# Portable_iron_V3_0.net
KiCad netlist of a schematic drawn in Altium Designer
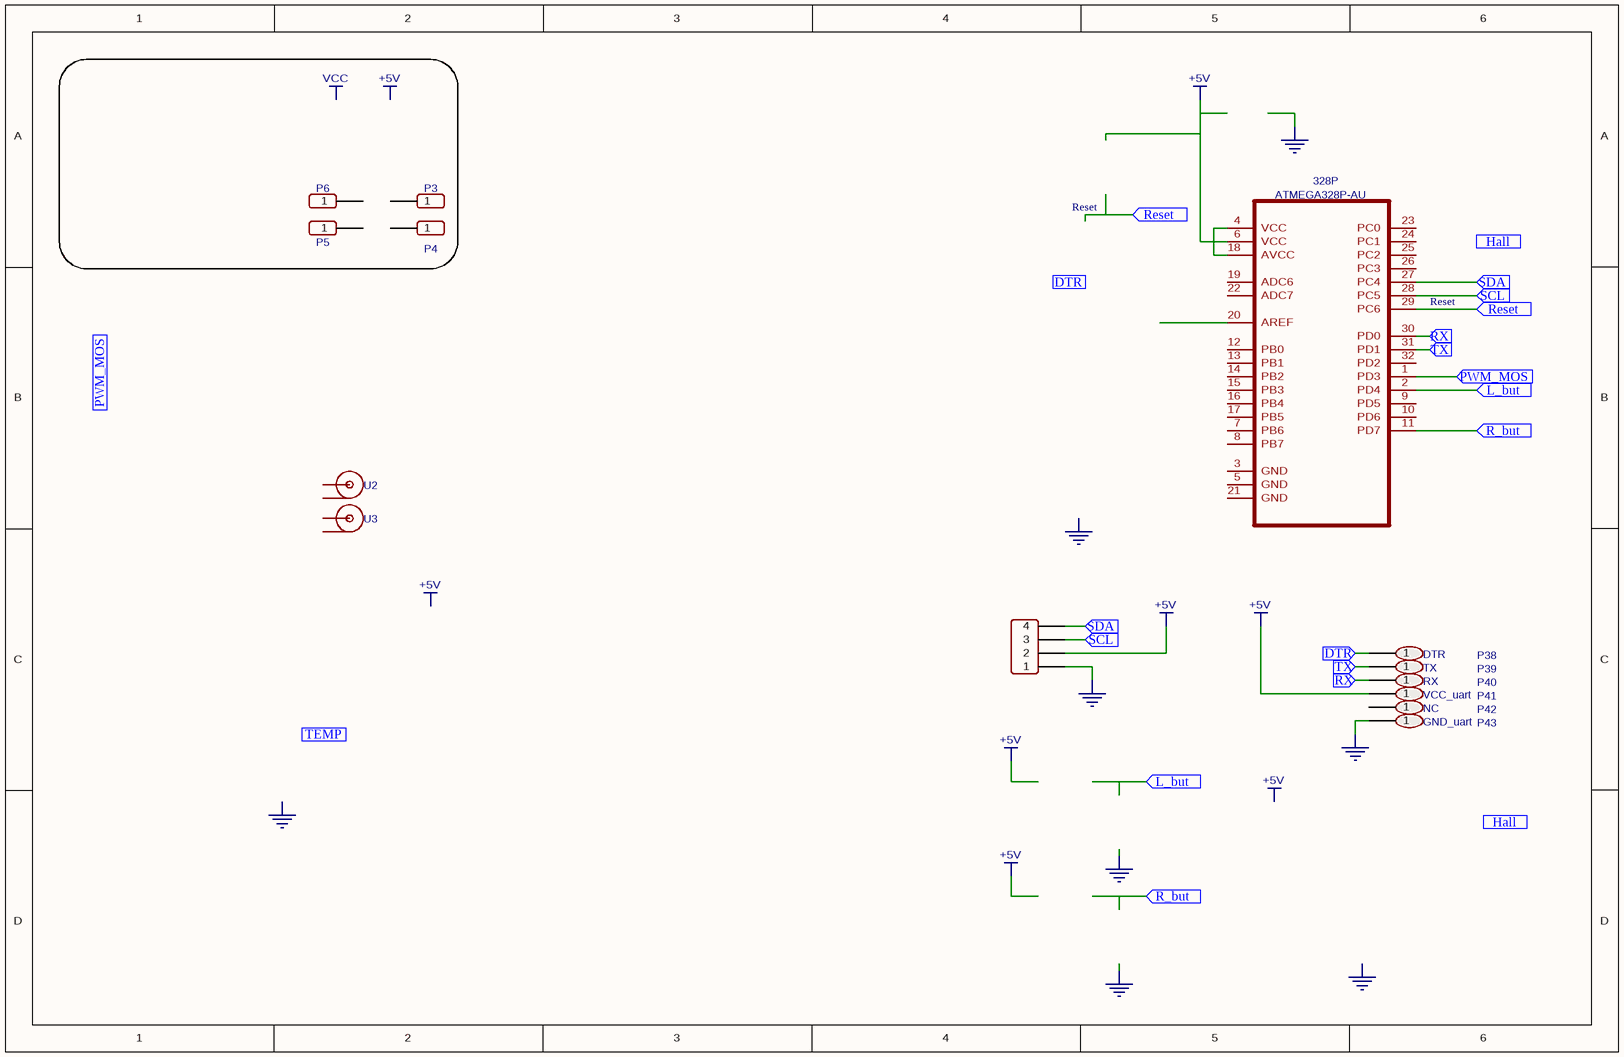
[diagram p0: Portable iron V3.0 .schdoc]

(export (version "E")
  (design (tool "Eeschema 10.0.6"))
  (components
    (comp (ref "328P")
      (value "ATMEGA328P-AU")
      (fields (field (name "BOM_MANUFACTURER PART") "?"))
      (libsource (lib "altium-import") (part "root_0_ATMEGA328P-AU_"))
    )
    (comp (ref "P1")
      (value "i2c_OLED")
      (fields
        (field (name "BOM_MANUFACTURER PART") "Headers  Pins 1*4P")
        (field (name "BOM_SUPPLIER PART") "undefined")
      )
      (libsource (lib "altium-import") (part "root_2_i2c_OLED_"))
    )
    (comp (ref "P3")
      (value "Header 1*1P")
      (fields (field (name "BOM_SUPPLIER PART") "C81276"))
      (libsource (lib "altium-import") (part "root_0_Header 1*1P_"))
    )
    (comp (ref "P4")
      (value "Header 1*1P")
      (fields (field (name "BOM_SUPPLIER PART") "C81276"))
      (libsource (lib "altium-import") (part "root_0_Header 1*1P_"))
    )
    (comp (ref "P5")
      (value "Header 1*1P")
      (fields (field (name "BOM_SUPPLIER PART") "C81276"))
      (libsource (lib "altium-import") (part "root_2_Header 1*1P_"))
    )
    (comp (ref "P6")
      (value "Header 1*1P")
      (fields (field (name "BOM_SUPPLIER PART") "C81276"))
      (libsource (lib "altium-import") (part "root_2_Header 1*1P_"))
    )
    (comp (ref "P38")
      (value "DTR")
      (fields
        (field (name "BOM_MANUFACTURER PART") "Header 1*1P")
        (field (name "BOM_SUPPLIER PART") "C81276")
      )
      (libsource (lib "altium-import") (part "root_0_DTR_"))
    )
    (comp (ref "P39")
      (value "TX")
      (fields
        (field (name "BOM_MANUFACTURER PART") "Header 1*1P")
        (field (name "BOM_SUPPLIER PART") "C81276")
      )
      (libsource (lib "altium-import") (part "root_0_TX_"))
    )
    (comp (ref "P40")
      (value "RX")
      (fields
        (field (name "BOM_MANUFACTURER PART") "Header 1*1P")
        (field (name "BOM_SUPPLIER PART") "C81276")
      )
      (libsource (lib "altium-import") (part "root_0_RX_"))
    )
    (comp (ref "P41")
      (value "VCC_uart")
      (fields
        (field (name "BOM_MANUFACTURER PART") "Header 1*1P")
        (field (name "BOM_SUPPLIER PART") "C81276")
      )
      (libsource (lib "altium-import") (part "root_0_VCC_uart_"))
    )
    (comp (ref "P42")
      (value "NC")
      (fields
        (field (name "BOM_MANUFACTURER PART") "Header 1*1P")
        (field (name "BOM_SUPPLIER PART") "C81276")
      )
      (libsource (lib "altium-import") (part "root_0_NC_"))
    )
    (comp (ref "P43")
      (value "GND_uart")
      (fields
        (field (name "BOM_MANUFACTURER PART") "Header 1*1P")
        (field (name "BOM_SUPPLIER PART") "C81276")
      )
      (libsource (lib "altium-import") (part "root_0_GND_uart_"))
    )
    (comp (ref "U2")
      (value "Fuse clip 1p TH")
      (fields
        (field (name "BOM_MANUFACTURER PART") "5x20 RHOS Fuse clip/seat")
        (field (name "BOM_SUPPLIER PART") "C3130")
        (field (name "CONTRIBUTOR") "gjt211")
      )
      (libsource (lib "altium-import") (part "root_0_Fuse clip 1p TH_"))
    )
    (comp (ref "U3")
      (value "Fuse clip 1p TH")
      (fields
        (field (name "BOM_MANUFACTURER PART") "5x20 RHOS Fuse clip/seat")
        (field (name "BOM_SUPPLIER PART") "C3130")
        (field (name "CONTRIBUTOR") "gjt211")
      )
      (libsource (lib "altium-import") (part "root_0_Fuse clip 1p TH_"))
    )
  )
  (nets
    (net (code "1") (name "+5V") (class "Default")
      (node (ref "328P") (pin "18") (pinfunction "AVCC_18") (pintype "passive"))
      (node (ref "328P") (pin "4") (pinfunction "VCC_4") (pintype "passive"))
      (node (ref "328P") (pin "6") (pinfunction "VCC_6") (pintype "passive"))
      (node (ref "P1") (pin "2") (pinfunction "2_2") (pintype "passive"))
      (node (ref "P41") (pin "1") (pinfunction "1_1") (pintype "passive"))
    )
    (net (code "2") (name "/DTR") (class "Default")
      (node (ref "P38") (pin "1") (pinfunction "1_1") (pintype "passive"))
    )
    (net (code "4") (name "/L_but") (class "Default")
      (node (ref "328P") (pin "2") (pinfunction "PD4_2") (pintype "passive"))
    )
    (net (code "5") (name "/PWM_MOS") (class "Default")
      (node (ref "328P") (pin "1") (pinfunction "PD3_1") (pintype "passive"))
    )
    (net (code "6") (name "/RX") (class "Default")
      (node (ref "328P") (pin "30") (pinfunction "PD0_30") (pintype "passive"))
      (node (ref "P40") (pin "1") (pinfunction "1_1") (pintype "passive"))
    )
    (net (code "7") (name "/R_but") (class "Default")
      (node (ref "328P") (pin "11") (pinfunction "PD7_11") (pintype "passive"))
    )
    (net (code "8") (name "/Reset") (class "Default")
      (node (ref "328P") (pin "29") (pinfunction "PC6_29") (pintype "passive"))
    )
    (net (code "9") (name "/SCL") (class "Default")
      (node (ref "328P") (pin "28") (pinfunction "PC5_28") (pintype "passive"))
      (node (ref "P1") (pin "3") (pinfunction "3_3") (pintype "passive"))
    )
    (net (code "10") (name "/SDA") (class "Default")
      (node (ref "328P") (pin "27") (pinfunction "PC4_27") (pintype "passive"))
      (node (ref "P1") (pin "4") (pinfunction "4_4") (pintype "passive"))
    )
    (net (code "12") (name "/TX") (class "Default")
      (node (ref "328P") (pin "31") (pinfunction "PD1_31") (pintype "passive"))
      (node (ref "P39") (pin "1") (pinfunction "1_1") (pintype "passive"))
    )
    (net (code "13") (name "GND") (class "Default")
      (node (ref "P1") (pin "1") (pinfunction "1_1") (pintype "passive"))
      (node (ref "P43") (pin "1") (pinfunction "1_1") (pintype "passive"))
    )
    (net (code "15") (name "unconnected-(328P-ADC6-Pad19)") (class "Default")
      (node (ref "328P") (pin "19") (pinfunction "ADC6_19") (pintype "passive"))
    )
    (net (code "16") (name "unconnected-(328P-ADC7-Pad22)") (class "Default")
      (node (ref "328P") (pin "22") (pinfunction "ADC7_22") (pintype "passive"))
    )
    (net (code "17") (name "unconnected-(328P-AREF-Pad20)") (class "Default")
      (node (ref "328P") (pin "20") (pinfunction "AREF_20") (pintype "passive"))
    )
    (net (code "18") (name "unconnected-(328P-GND-Pad3)") (class "Default")
      (node (ref "328P") (pin "3") (pinfunction "GND_3") (pintype "passive"))
    )
    (net (code "19") (name "unconnected-(328P-GND-Pad5)") (class "Default")
      (node (ref "328P") (pin "5") (pinfunction "GND_5") (pintype "passive"))
    )
    (net (code "20") (name "unconnected-(328P-GND-Pad21)") (class "Default")
      (node (ref "328P") (pin "21") (pinfunction "GND_21") (pintype "passive"))
    )
    (net (code "21") (name "unconnected-(328P-PB0-Pad12)") (class "Default")
      (node (ref "328P") (pin "12") (pinfunction "PB0_12") (pintype "passive"))
    )
    (net (code "22") (name "unconnected-(328P-PB1-Pad13)") (class "Default")
      (node (ref "328P") (pin "13") (pinfunction "PB1_13") (pintype "passive"))
    )
    (net (code "23") (name "unconnected-(328P-PB2-Pad14)") (class "Default")
      (node (ref "328P") (pin "14") (pinfunction "PB2_14") (pintype "passive"))
    )
    (net (code "24") (name "unconnected-(328P-PB3-Pad15)") (class "Default")
      (node (ref "328P") (pin "15") (pinfunction "PB3_15") (pintype "passive"))
    )
    (net (code "25") (name "unconnected-(328P-PB4-Pad16)") (class "Default")
      (node (ref "328P") (pin "16") (pinfunction "PB4_16") (pintype "passive"))
    )
    (net (code "26") (name "unconnected-(328P-PB5-Pad17)") (class "Default")
      (node (ref "328P") (pin "17") (pinfunction "PB5_17") (pintype "passive"))
    )
    (net (code "27") (name "unconnected-(328P-PB6-Pad7)") (class "Default")
      (node (ref "328P") (pin "7") (pinfunction "PB6_7") (pintype "passive"))
    )
    (net (code "28") (name "unconnected-(328P-PB7-Pad8)") (class "Default")
      (node (ref "328P") (pin "8") (pinfunction "PB7_8") (pintype "passive"))
    )
    (net (code "29") (name "unconnected-(328P-PC0-Pad23)") (class "Default")
      (node (ref "328P") (pin "23") (pinfunction "PC0_23") (pintype "passive"))
    )
    (net (code "30") (name "unconnected-(328P-PC1-Pad24)") (class "Default")
      (node (ref "328P") (pin "24") (pinfunction "PC1_24") (pintype "passive"))
    )
    (net (code "31") (name "unconnected-(328P-PC2-Pad25)") (class "Default")
      (node (ref "328P") (pin "25") (pinfunction "PC2_25") (pintype "passive"))
    )
    (net (code "32") (name "unconnected-(328P-PC3-Pad26)") (class "Default")
      (node (ref "328P") (pin "26") (pinfunction "PC3_26") (pintype "passive"))
    )
    (net (code "33") (name "unconnected-(328P-PD2-Pad32)") (class "Default")
      (node (ref "328P") (pin "32") (pinfunction "PD2_32") (pintype "passive"))
    )
    (net (code "34") (name "unconnected-(328P-PD5-Pad9)") (class "Default")
      (node (ref "328P") (pin "9") (pinfunction "PD5_9") (pintype "passive"))
    )
    (net (code "35") (name "unconnected-(328P-PD6-Pad10)") (class "Default")
      (node (ref "328P") (pin "10") (pinfunction "PD6_10") (pintype "passive"))
    )
    (net (code "36") (name "unconnected-(P3-Pad1)") (class "Default")
      (node (ref "P3") (pin "1") (pinfunction "1_1") (pintype "passive"))
    )
    (net (code "37") (name "unconnected-(P4-Pad1)") (class "Default")
      (node (ref "P4") (pin "1") (pinfunction "1_1") (pintype "passive"))
    )
    (net (code "38") (name "unconnected-(P5-Pad1)") (class "Default")
      (node (ref "P5") (pin "1") (pinfunction "1_1") (pintype "passive"))
    )
    (net (code "39") (name "unconnected-(P6-Pad1)") (class "Default")
      (node (ref "P6") (pin "1") (pinfunction "1_1") (pintype "passive"))
    )
    (net (code "40") (name "unconnected-(P42-Pad1)") (class "Default")
      (node (ref "P42") (pin "1") (pinfunction "1_1") (pintype "passive"))
    )
    (net (code "41") (name "unconnected-(U2-Pad1)") (class "Default")
      (node (ref "U2") (pin "1") (pinfunction "1_1") (pintype "passive"))
    )
    (net (code "42") (name "unconnected-(U2-Pad1)_1") (class "Default")
      (node (ref "U2") (pin "1") (pinfunction "1_1") (pintype "passive"))
    )
    (net (code "43") (name "unconnected-(U3-Pad1)") (class "Default")
      (node (ref "U3") (pin "1") (pinfunction "1_1") (pintype "passive"))
    )
    (net (code "44") (name "unconnected-(U3-Pad1)_1") (class "Default")
      (node (ref "U3") (pin "1") (pinfunction "1_1") (pintype "passive"))
    )
  )
)
